# NodeMCU_i2c_1wire_Breakout.net
KiCad netlist of a schematic drawn in EAGLE
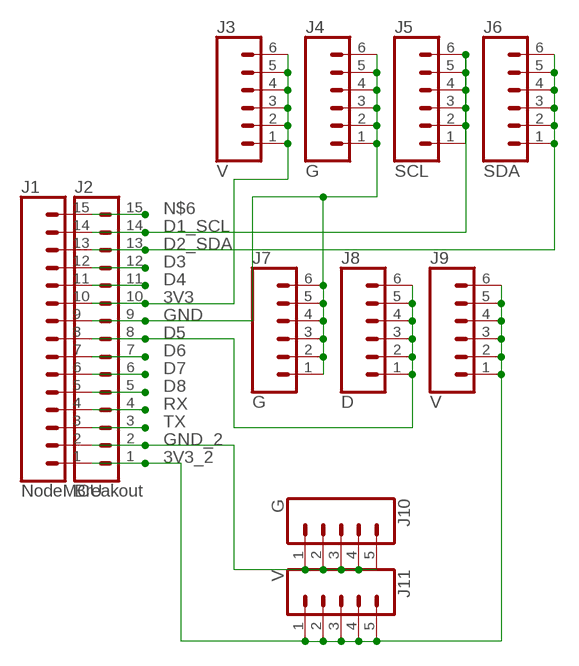
[diagram p0: schematic, sheet 1]

(export (version "E")
  (design (tool "Eeschema 10.0.6"))
  (components
    (comp (ref "J1")
      (value "NodeMCU")
      (footprint "eagle-import:1X15")
      (libsource (lib "eagle-import") (part "CONN_15"))
    )
    (comp (ref "J2")
      (value "Breakout")
      (footprint "eagle-import:1X15")
      (libsource (lib "eagle-import") (part "CONN_15"))
    )
    (comp (ref "J3")
      (value "V")
      (footprint "eagle-import:1X06")
      (libsource (lib "eagle-import") (part "CONN_06SILK_FEMALE_PTH"))
    )
    (comp (ref "J4")
      (value "G")
      (footprint "eagle-import:1X06")
      (libsource (lib "eagle-import") (part "CONN_06SILK_FEMALE_PTH"))
    )
    (comp (ref "J5")
      (value "SCL")
      (footprint "eagle-import:1X06")
      (libsource (lib "eagle-import") (part "CONN_06SILK_FEMALE_PTH"))
    )
    (comp (ref "J6")
      (value "SDA")
      (footprint "eagle-import:1X06")
      (libsource (lib "eagle-import") (part "CONN_06SILK_FEMALE_PTH"))
    )
    (comp (ref "J7")
      (value "G")
      (footprint "eagle-import:1X06")
      (libsource (lib "eagle-import") (part "CONN_06SILK_FEMALE_PTH"))
    )
    (comp (ref "J8")
      (value "D")
      (footprint "eagle-import:1X06")
      (libsource (lib "eagle-import") (part "CONN_06SILK_FEMALE_PTH"))
    )
    (comp (ref "J9")
      (value "V")
      (footprint "eagle-import:1X06")
      (libsource (lib "eagle-import") (part "CONN_06SILK_FEMALE_PTH"))
    )
    (comp (ref "J10")
      (value "G")
      (footprint "eagle-import:1X05")
      (libsource (lib "eagle-import") (part "CONN_05"))
    )
    (comp (ref "J11")
      (value "V")
      (footprint "eagle-import:1X05")
      (libsource (lib "eagle-import") (part "CONN_05"))
    )
  )
  (nets
    (net (code "1") (name "/3V3") (class "Default")
      (node (ref "J1") (pin "10") (pinfunction "10_10") (pintype "passive"))
      (node (ref "J2") (pin "10") (pinfunction "10_10") (pintype "passive"))
      (node (ref "J3") (pin "1") (pinfunction "1_1") (pintype "passive"))
      (node (ref "J3") (pin "2") (pinfunction "2_2") (pintype "passive"))
      (node (ref "J3") (pin "3") (pinfunction "3_3") (pintype "passive"))
      (node (ref "J3") (pin "4") (pinfunction "4_4") (pintype "passive"))
      (node (ref "J3") (pin "5") (pinfunction "5_5") (pintype "passive"))
      (node (ref "J3") (pin "6") (pinfunction "6_6") (pintype "passive"))
    )
    (net (code "2") (name "/3V3_2") (class "Default")
      (node (ref "J1") (pin "1") (pinfunction "1_1") (pintype "passive"))
      (node (ref "J11") (pin "1") (pinfunction "1_1") (pintype "passive"))
      (node (ref "J11") (pin "2") (pinfunction "2_2") (pintype "passive"))
      (node (ref "J11") (pin "3") (pinfunction "3_3") (pintype "passive"))
      (node (ref "J11") (pin "4") (pinfunction "4_4") (pintype "passive"))
      (node (ref "J11") (pin "5") (pinfunction "5_5") (pintype "passive"))
      (node (ref "J2") (pin "1") (pinfunction "1_1") (pintype "passive"))
      (node (ref "J9") (pin "1") (pinfunction "1_1") (pintype "passive"))
      (node (ref "J9") (pin "2") (pinfunction "2_2") (pintype "passive"))
      (node (ref "J9") (pin "3") (pinfunction "3_3") (pintype "passive"))
      (node (ref "J9") (pin "4") (pinfunction "4_4") (pintype "passive"))
      (node (ref "J9") (pin "5") (pinfunction "5_5") (pintype "passive"))
      (node (ref "J9") (pin "6") (pinfunction "6_6") (pintype "passive"))
    )
    (net (code "3") (name "/D1_SCL") (class "Default")
      (node (ref "J1") (pin "14") (pinfunction "14_14") (pintype "passive"))
      (node (ref "J2") (pin "14") (pinfunction "14_14") (pintype "passive"))
      (node (ref "J5") (pin "1") (pinfunction "1_1") (pintype "passive"))
      (node (ref "J5") (pin "2") (pinfunction "2_2") (pintype "passive"))
      (node (ref "J5") (pin "3") (pinfunction "3_3") (pintype "passive"))
      (node (ref "J5") (pin "4") (pinfunction "4_4") (pintype "passive"))
      (node (ref "J5") (pin "5") (pinfunction "5_5") (pintype "passive"))
      (node (ref "J5") (pin "6") (pinfunction "6_6") (pintype "passive"))
    )
    (net (code "4") (name "/D2_SDA") (class "Default")
      (node (ref "J1") (pin "13") (pinfunction "13_13") (pintype "passive"))
      (node (ref "J2") (pin "13") (pinfunction "13_13") (pintype "passive"))
      (node (ref "J6") (pin "1") (pinfunction "1_1") (pintype "passive"))
      (node (ref "J6") (pin "2") (pinfunction "2_2") (pintype "passive"))
      (node (ref "J6") (pin "3") (pinfunction "3_3") (pintype "passive"))
      (node (ref "J6") (pin "4") (pinfunction "4_4") (pintype "passive"))
      (node (ref "J6") (pin "5") (pinfunction "5_5") (pintype "passive"))
      (node (ref "J6") (pin "6") (pinfunction "6_6") (pintype "passive"))
    )
    (net (code "5") (name "/D3") (class "Default")
      (node (ref "J1") (pin "12") (pinfunction "12_12") (pintype "passive"))
      (node (ref "J2") (pin "12") (pinfunction "12_12") (pintype "passive"))
    )
    (net (code "6") (name "/D4") (class "Default")
      (node (ref "J1") (pin "11") (pinfunction "11_11") (pintype "passive"))
      (node (ref "J2") (pin "11") (pinfunction "11_11") (pintype "passive"))
    )
    (net (code "7") (name "/D5") (class "Default")
      (node (ref "J1") (pin "8") (pinfunction "8_8") (pintype "passive"))
      (node (ref "J2") (pin "8") (pinfunction "8_8") (pintype "passive"))
      (node (ref "J8") (pin "1") (pinfunction "1_1") (pintype "passive"))
      (node (ref "J8") (pin "2") (pinfunction "2_2") (pintype "passive"))
      (node (ref "J8") (pin "3") (pinfunction "3_3") (pintype "passive"))
      (node (ref "J8") (pin "4") (pinfunction "4_4") (pintype "passive"))
      (node (ref "J8") (pin "5") (pinfunction "5_5") (pintype "passive"))
      (node (ref "J8") (pin "6") (pinfunction "6_6") (pintype "passive"))
    )
    (net (code "8") (name "/D6") (class "Default")
      (node (ref "J1") (pin "7") (pinfunction "7_7") (pintype "passive"))
      (node (ref "J2") (pin "7") (pinfunction "7_7") (pintype "passive"))
    )
    (net (code "9") (name "/D7") (class "Default")
      (node (ref "J1") (pin "6") (pinfunction "6_6") (pintype "passive"))
      (node (ref "J2") (pin "6") (pinfunction "6_6") (pintype "passive"))
    )
    (net (code "10") (name "/D8") (class "Default")
      (node (ref "J1") (pin "5") (pinfunction "5_5") (pintype "passive"))
      (node (ref "J2") (pin "5") (pinfunction "5_5") (pintype "passive"))
    )
    (net (code "11") (name "/GND") (class "Default")
      (node (ref "J1") (pin "9") (pinfunction "9_9") (pintype "passive"))
      (node (ref "J2") (pin "9") (pinfunction "9_9") (pintype "passive"))
      (node (ref "J4") (pin "1") (pinfunction "1_1") (pintype "passive"))
      (node (ref "J4") (pin "2") (pinfunction "2_2") (pintype "passive"))
      (node (ref "J4") (pin "3") (pinfunction "3_3") (pintype "passive"))
      (node (ref "J4") (pin "4") (pinfunction "4_4") (pintype "passive"))
      (node (ref "J4") (pin "5") (pinfunction "5_5") (pintype "passive"))
      (node (ref "J4") (pin "6") (pinfunction "6_6") (pintype "passive"))
      (node (ref "J7") (pin "1") (pinfunction "1_1") (pintype "passive"))
      (node (ref "J7") (pin "2") (pinfunction "2_2") (pintype "passive"))
      (node (ref "J7") (pin "3") (pinfunction "3_3") (pintype "passive"))
      (node (ref "J7") (pin "4") (pinfunction "4_4") (pintype "passive"))
      (node (ref "J7") (pin "5") (pinfunction "5_5") (pintype "passive"))
      (node (ref "J7") (pin "6") (pinfunction "6_6") (pintype "passive"))
    )
    (net (code "12") (name "/GND_2") (class "Default")
      (node (ref "J1") (pin "2") (pinfunction "2_2") (pintype "passive"))
      (node (ref "J10") (pin "1") (pinfunction "1_1") (pintype "passive"))
      (node (ref "J10") (pin "2") (pinfunction "2_2") (pintype "passive"))
      (node (ref "J10") (pin "3") (pinfunction "3_3") (pintype "passive"))
      (node (ref "J10") (pin "4") (pinfunction "4_4") (pintype "passive"))
      (node (ref "J10") (pin "5") (pinfunction "5_5") (pintype "passive"))
      (node (ref "J2") (pin "2") (pinfunction "2_2") (pintype "passive"))
    )
    (net (code "13") (name "/N$6") (class "Default")
      (node (ref "J1") (pin "15") (pinfunction "15_15") (pintype "passive"))
      (node (ref "J2") (pin "15") (pinfunction "15_15") (pintype "passive"))
    )
    (net (code "14") (name "/RX") (class "Default")
      (node (ref "J1") (pin "4") (pinfunction "4_4") (pintype "passive"))
      (node (ref "J2") (pin "4") (pinfunction "4_4") (pintype "passive"))
    )
    (net (code "15") (name "/TX") (class "Default")
      (node (ref "J1") (pin "3") (pinfunction "3_3") (pintype "passive"))
      (node (ref "J2") (pin "3") (pinfunction "3_3") (pintype "passive"))
    )
  )
)
